# numpad.net
KiCad netlist of a schematic drawn in EAGLE
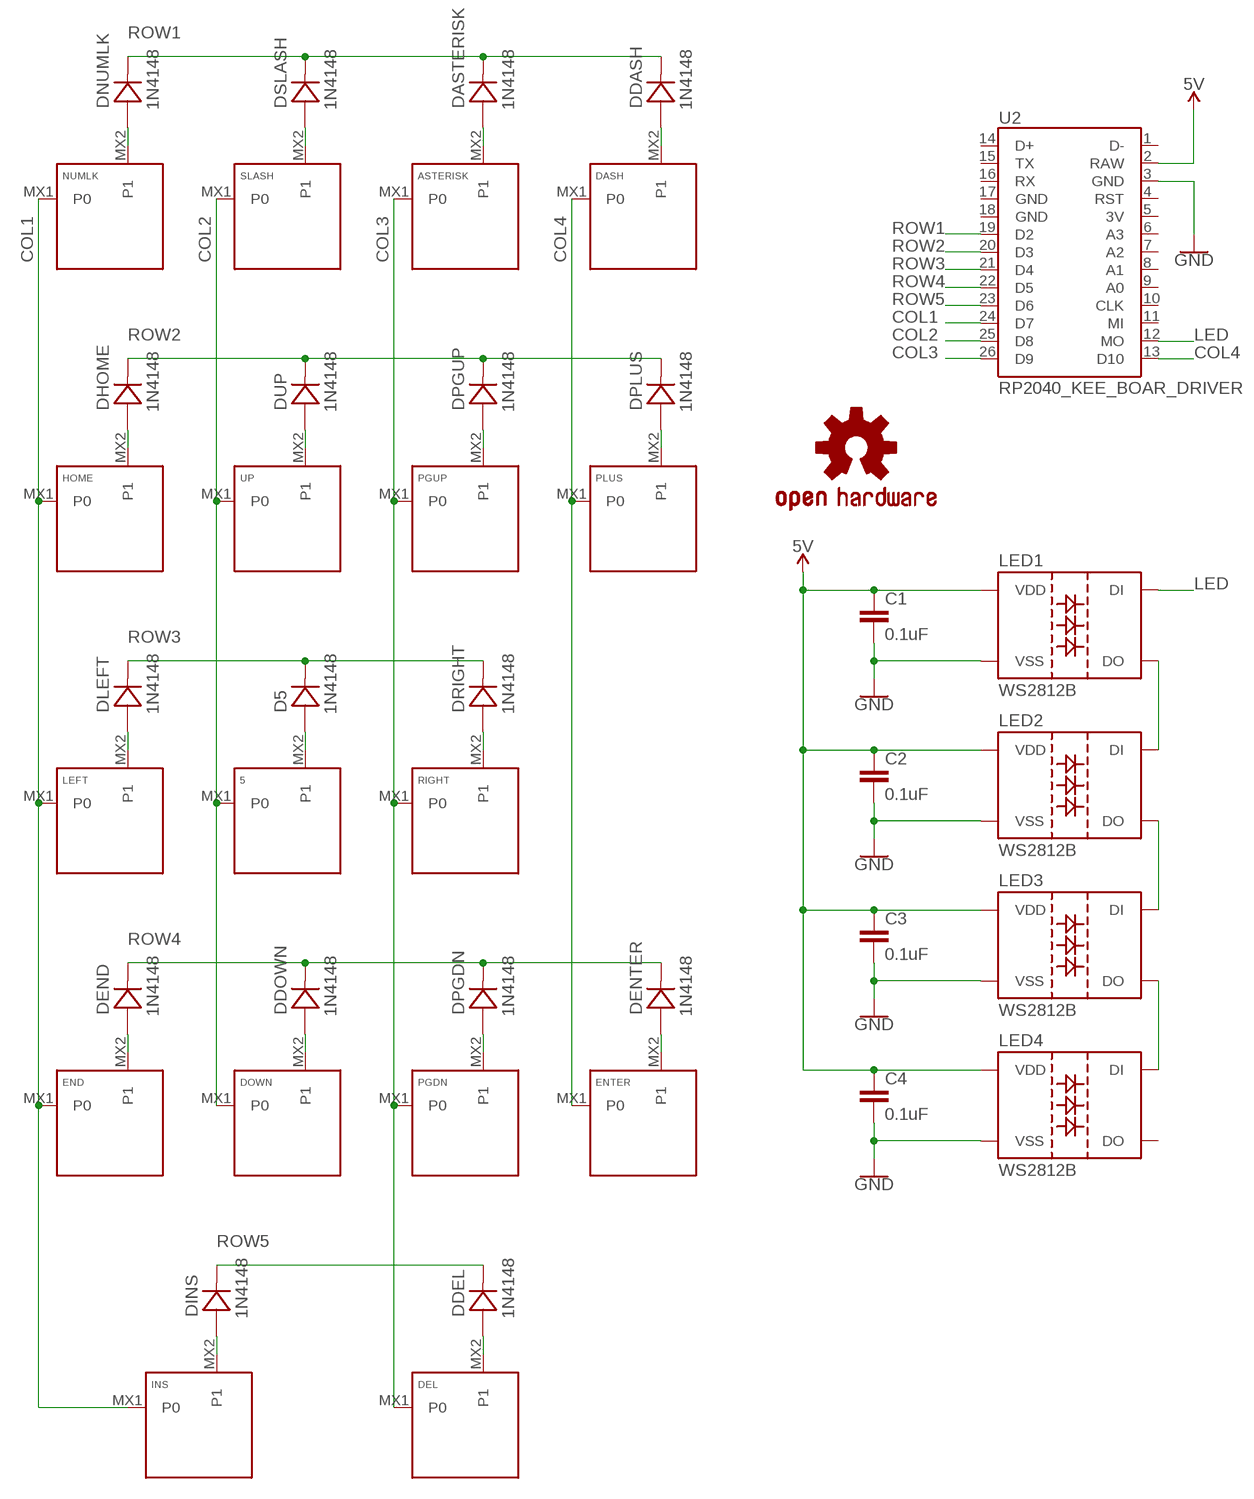
[diagram p0: schematic, sheet 1]

(export (version "E")
  (design (tool "Eeschema 10.0.6"))
  (components
    (comp (ref "5")
      (value "KEYSWITCH-PLAIN-MXHSPCB-1U")
      (footprint "eagle-import:MXHSPCB-1U")
      (libsource (lib "eagle-import") (part "KEYSWITCH-PLAIN-MXHSPCB-1U"))
    )
    (comp (ref "ASTERISK")
      (value "KEYSWITCH-PLAIN-MXHSPCB-1U")
      (footprint "eagle-import:MXHSPCB-1U")
      (libsource (lib "eagle-import") (part "KEYSWITCH-PLAIN-MXHSPCB-1U"))
    )
    (comp (ref "C1")
      (value "0.1uF")
      (footprint "eagle-import:0603")
      (libsource (lib "eagle-import") (part "0.1UF-0603-25V-(+80/-20%)"))
    )
    (comp (ref "C2")
      (value "0.1uF")
      (footprint "eagle-import:0603")
      (libsource (lib "eagle-import") (part "0.1UF-0603-25V-(+80/-20%)"))
    )
    (comp (ref "C3")
      (value "0.1uF")
      (footprint "eagle-import:0603")
      (libsource (lib "eagle-import") (part "0.1UF-0603-25V-(+80/-20%)"))
    )
    (comp (ref "C4")
      (value "0.1uF")
      (footprint "eagle-import:0603")
      (libsource (lib "eagle-import") (part "0.1UF-0603-25V-(+80/-20%)"))
    )
    (comp (ref "D5")
      (value "1N4148")
      (footprint "eagle-import:DO-35")
      (libsource (lib "eagle-import") (part "DIODE-DO-35"))
    )
    (comp (ref "DASH")
      (value "KEYSWITCH-PLAIN-MXHSPCB-1U")
      (footprint "eagle-import:MXHSPCB-1U")
      (libsource (lib "eagle-import") (part "KEYSWITCH-PLAIN-MXHSPCB-1U"))
    )
    (comp (ref "DASTERISK")
      (value "1N4148")
      (footprint "eagle-import:DO-35")
      (libsource (lib "eagle-import") (part "DIODE-DO-35"))
    )
    (comp (ref "DDASH")
      (value "1N4148")
      (footprint "eagle-import:DO-35")
      (libsource (lib "eagle-import") (part "DIODE-DO-35"))
    )
    (comp (ref "DDEL")
      (value "1N4148")
      (footprint "eagle-import:DO-35")
      (libsource (lib "eagle-import") (part "DIODE-DO-35"))
    )
    (comp (ref "DDOWN")
      (value "1N4148")
      (footprint "eagle-import:DO-35")
      (libsource (lib "eagle-import") (part "DIODE-DO-35"))
    )
    (comp (ref "DEL")
      (value "KEYSWITCH-PLAIN-MXHSPCB-1U")
      (footprint "eagle-import:MXHSPCB-1U")
      (libsource (lib "eagle-import") (part "KEYSWITCH-PLAIN-MXHSPCB-1U"))
    )
    (comp (ref "DEND")
      (value "1N4148")
      (footprint "eagle-import:DO-35")
      (libsource (lib "eagle-import") (part "DIODE-DO-35"))
    )
    (comp (ref "DENTER")
      (value "1N4148")
      (footprint "eagle-import:DO-35")
      (libsource (lib "eagle-import") (part "DIODE-DO-35"))
    )
    (comp (ref "DHOME")
      (value "1N4148")
      (footprint "eagle-import:DO-35")
      (libsource (lib "eagle-import") (part "DIODE-DO-35"))
    )
    (comp (ref "DINS")
      (value "1N4148")
      (footprint "eagle-import:DO-35")
      (libsource (lib "eagle-import") (part "DIODE-DO-35"))
    )
    (comp (ref "DLEFT")
      (value "1N4148")
      (footprint "eagle-import:DO-35")
      (libsource (lib "eagle-import") (part "DIODE-DO-35"))
    )
    (comp (ref "DNUMLK")
      (value "1N4148")
      (footprint "eagle-import:DO-35")
      (libsource (lib "eagle-import") (part "DIODE-DO-35"))
    )
    (comp (ref "DOWN")
      (value "KEYSWITCH-PLAIN-MXHSPCB-1U")
      (footprint "eagle-import:MXHSPCB-1U")
      (libsource (lib "eagle-import") (part "KEYSWITCH-PLAIN-MXHSPCB-1U"))
    )
    (comp (ref "DPGDN")
      (value "1N4148")
      (footprint "eagle-import:DO-35")
      (libsource (lib "eagle-import") (part "DIODE-DO-35"))
    )
    (comp (ref "DPGUP")
      (value "1N4148")
      (footprint "eagle-import:DO-35")
      (libsource (lib "eagle-import") (part "DIODE-DO-35"))
    )
    (comp (ref "DPLUS")
      (value "1N4148")
      (footprint "eagle-import:DO-35")
      (libsource (lib "eagle-import") (part "DIODE-DO-35"))
    )
    (comp (ref "DRIGHT")
      (value "1N4148")
      (footprint "eagle-import:DO-35")
      (libsource (lib "eagle-import") (part "DIODE-DO-35"))
    )
    (comp (ref "DSLASH")
      (value "1N4148")
      (footprint "eagle-import:DO-35")
      (libsource (lib "eagle-import") (part "DIODE-DO-35"))
    )
    (comp (ref "DUP")
      (value "1N4148")
      (footprint "eagle-import:DO-35")
      (libsource (lib "eagle-import") (part "DIODE-DO-35"))
    )
    (comp (ref "END")
      (value "KEYSWITCH-PLAIN-MXHSPCB-1U")
      (footprint "eagle-import:MXHSPCB-1U")
      (libsource (lib "eagle-import") (part "KEYSWITCH-PLAIN-MXHSPCB-1U"))
    )
    (comp (ref "ENTER")
      (value "KEYSWITCH-PLAIN-MXHSPCB-2U-ROTATED")
      (footprint "eagle-import:MXHSPCB-2U-ROTATED")
      (libsource (lib "eagle-import") (part "KEYSWITCH-PLAIN-MXHSPCB-2U-ROTATED"))
    )
    (comp (ref "HOME")
      (value "KEYSWITCH-PLAIN-MXHSPCB-1U")
      (footprint "eagle-import:MXHSPCB-1U")
      (libsource (lib "eagle-import") (part "KEYSWITCH-PLAIN-MXHSPCB-1U"))
    )
    (comp (ref "INS")
      (value "KEYSWITCH-PLAIN-MXHSPCB-2U")
      (footprint "eagle-import:MXHSPCB-2U")
      (libsource (lib "eagle-import") (part "KEYSWITCH-PLAIN-MXHSPCB-2U"))
    )
    (comp (ref "LED1")
      (value "WS2812B")
      (footprint "eagle-import:WS2812B")
      (libsource (lib "eagle-import") (part "WS2812B"))
    )
    (comp (ref "LED2")
      (value "WS2812B")
      (footprint "eagle-import:WS2812B")
      (libsource (lib "eagle-import") (part "WS2812B"))
    )
    (comp (ref "LED3")
      (value "WS2812B")
      (footprint "eagle-import:WS2812B")
      (libsource (lib "eagle-import") (part "WS2812B"))
    )
    (comp (ref "LED4")
      (value "WS2812B")
      (footprint "eagle-import:WS2812B")
      (libsource (lib "eagle-import") (part "WS2812B"))
    )
    (comp (ref "LEFT")
      (value "KEYSWITCH-PLAIN-MXHSPCB-1U")
      (footprint "eagle-import:MXHSPCB-1U")
      (libsource (lib "eagle-import") (part "KEYSWITCH-PLAIN-MXHSPCB-1U"))
    )
    (comp (ref "LOGO1")
      (value "OSHW-LOGOM")
      (footprint "eagle-import:OSHW-LOGO-M")
      (libsource (lib "eagle-import") (part "OSHW-LOGOM"))
    )
    (comp (ref "NUMLK")
      (value "KEYSWITCH-PLAIN-MXHSPCB-1U")
      (footprint "eagle-import:MXHSPCB-1U")
      (libsource (lib "eagle-import") (part "KEYSWITCH-PLAIN-MXHSPCB-1U"))
    )
    (comp (ref "PGDN")
      (value "KEYSWITCH-PLAIN-MXHSPCB-1U")
      (footprint "eagle-import:MXHSPCB-1U")
      (libsource (lib "eagle-import") (part "KEYSWITCH-PLAIN-MXHSPCB-1U"))
    )
    (comp (ref "PGUP")
      (value "KEYSWITCH-PLAIN-MXHSPCB-1U")
      (footprint "eagle-import:MXHSPCB-1U")
      (libsource (lib "eagle-import") (part "KEYSWITCH-PLAIN-MXHSPCB-1U"))
    )
    (comp (ref "PLUS")
      (value "KEYSWITCH-PLAIN-MXHSPCB-2U-ROTATED")
      (footprint "eagle-import:MXHSPCB-2U-ROTATED")
      (libsource (lib "eagle-import") (part "KEYSWITCH-PLAIN-MXHSPCB-2U-ROTATED"))
    )
    (comp (ref "RIGHT")
      (value "KEYSWITCH-PLAIN-MXHSPCB-1U")
      (footprint "eagle-import:MXHSPCB-1U")
      (libsource (lib "eagle-import") (part "KEYSWITCH-PLAIN-MXHSPCB-1U"))
    )
    (comp (ref "SLASH")
      (value "KEYSWITCH-PLAIN-MXHSPCB-1U")
      (footprint "eagle-import:MXHSPCB-1U")
      (libsource (lib "eagle-import") (part "KEYSWITCH-PLAIN-MXHSPCB-1U"))
    )
    (comp (ref "U2")
      (value "RP2040_KEE_BOAR_DRIVER")
      (footprint "eagle-import:RP2040_KEE_BOAR_DRIVER")
      (libsource (lib "eagle-import") (part "RP2040_KEE_BOAR_DRIVER"))
    )
    (comp (ref "UP")
      (value "KEYSWITCH-PLAIN-MXHSPCB-1U")
      (footprint "eagle-import:MXHSPCB-1U")
      (libsource (lib "eagle-import") (part "KEYSWITCH-PLAIN-MXHSPCB-1U"))
    )
  )
  (nets
    (net (code "1") (name "/COL1") (class "Default")
      (node (ref "END") (pin "MX1") (pinfunction "P0_MX1") (pintype "bidirectional"))
      (node (ref "HOME") (pin "MX1") (pinfunction "P0_MX1") (pintype "bidirectional"))
      (node (ref "INS") (pin "MX1") (pinfunction "P0_MX1") (pintype "bidirectional"))
      (node (ref "LEFT") (pin "MX1") (pinfunction "P0_MX1") (pintype "bidirectional"))
      (node (ref "NUMLK") (pin "MX1") (pinfunction "P0_MX1") (pintype "bidirectional"))
      (node (ref "U2") (pin "24") (pinfunction "D7_24") (pintype "bidirectional"))
    )
    (net (code "2") (name "/COL2") (class "Default")
      (node (ref "5") (pin "MX1") (pinfunction "P0_MX1") (pintype "bidirectional"))
      (node (ref "DOWN") (pin "MX1") (pinfunction "P0_MX1") (pintype "bidirectional"))
      (node (ref "SLASH") (pin "MX1") (pinfunction "P0_MX1") (pintype "bidirectional"))
      (node (ref "U2") (pin "25") (pinfunction "D8_25") (pintype "bidirectional"))
      (node (ref "UP") (pin "MX1") (pinfunction "P0_MX1") (pintype "bidirectional"))
    )
    (net (code "3") (name "/COL3") (class "Default")
      (node (ref "ASTERISK") (pin "MX1") (pinfunction "P0_MX1") (pintype "bidirectional"))
      (node (ref "DEL") (pin "MX1") (pinfunction "P0_MX1") (pintype "bidirectional"))
      (node (ref "PGDN") (pin "MX1") (pinfunction "P0_MX1") (pintype "bidirectional"))
      (node (ref "PGUP") (pin "MX1") (pinfunction "P0_MX1") (pintype "bidirectional"))
      (node (ref "RIGHT") (pin "MX1") (pinfunction "P0_MX1") (pintype "bidirectional"))
      (node (ref "U2") (pin "26") (pinfunction "D9_26") (pintype "bidirectional"))
    )
    (net (code "4") (name "/COL4") (class "Default")
      (node (ref "DASH") (pin "MX1") (pinfunction "P0_MX1") (pintype "bidirectional"))
      (node (ref "ENTER") (pin "MX1") (pinfunction "P0_MX1") (pintype "bidirectional"))
      (node (ref "PLUS") (pin "MX1") (pinfunction "P0_MX1") (pintype "bidirectional"))
      (node (ref "U2") (pin "13") (pinfunction "D10_13") (pintype "bidirectional"))
    )
    (net (code "5") (name "/LED") (class "Default")
      (node (ref "LED1") (pin "4") (pinfunction "DI_4") (pintype "bidirectional"))
      (node (ref "U2") (pin "12") (pinfunction "MO_12") (pintype "bidirectional"))
    )
    (net (code "6") (name "/ROW1") (class "Default")
      (node (ref "DASTERISK") (pin "C") (pinfunction "C_C") (pintype "passive"))
      (node (ref "DDASH") (pin "C") (pinfunction "C_C") (pintype "passive"))
      (node (ref "DNUMLK") (pin "C") (pinfunction "C_C") (pintype "passive"))
      (node (ref "DSLASH") (pin "C") (pinfunction "C_C") (pintype "passive"))
      (node (ref "U2") (pin "19") (pinfunction "D2_19") (pintype "bidirectional"))
    )
    (net (code "7") (name "/ROW2") (class "Default")
      (node (ref "DHOME") (pin "C") (pinfunction "C_C") (pintype "passive"))
      (node (ref "DPGUP") (pin "C") (pinfunction "C_C") (pintype "passive"))
      (node (ref "DPLUS") (pin "C") (pinfunction "C_C") (pintype "passive"))
      (node (ref "DUP") (pin "C") (pinfunction "C_C") (pintype "passive"))
      (node (ref "U2") (pin "20") (pinfunction "D3_20") (pintype "bidirectional"))
    )
    (net (code "8") (name "/ROW3") (class "Default")
      (node (ref "D5") (pin "C") (pinfunction "C_C") (pintype "passive"))
      (node (ref "DLEFT") (pin "C") (pinfunction "C_C") (pintype "passive"))
      (node (ref "DRIGHT") (pin "C") (pinfunction "C_C") (pintype "passive"))
      (node (ref "U2") (pin "21") (pinfunction "D4_21") (pintype "bidirectional"))
    )
    (net (code "9") (name "/ROW4") (class "Default")
      (node (ref "DDOWN") (pin "C") (pinfunction "C_C") (pintype "passive"))
      (node (ref "DEND") (pin "C") (pinfunction "C_C") (pintype "passive"))
      (node (ref "DENTER") (pin "C") (pinfunction "C_C") (pintype "passive"))
      (node (ref "DPGDN") (pin "C") (pinfunction "C_C") (pintype "passive"))
      (node (ref "U2") (pin "22") (pinfunction "D5_22") (pintype "bidirectional"))
    )
    (net (code "10") (name "/ROW5") (class "Default")
      (node (ref "DDEL") (pin "C") (pinfunction "C_C") (pintype "passive"))
      (node (ref "DINS") (pin "C") (pinfunction "C_C") (pintype "passive"))
      (node (ref "U2") (pin "23") (pinfunction "D6_23") (pintype "bidirectional"))
    )
    (net (code "11") (name "5V") (class "Default")
      (node (ref "C1") (pin "1") (pinfunction "1_1") (pintype "passive"))
      (node (ref "C2") (pin "1") (pinfunction "1_1") (pintype "passive"))
      (node (ref "C3") (pin "1") (pinfunction "1_1") (pintype "passive"))
      (node (ref "C4") (pin "1") (pinfunction "1_1") (pintype "passive"))
      (node (ref "LED1") (pin "1") (pinfunction "VDD_1") (pintype "bidirectional"))
      (node (ref "LED2") (pin "1") (pinfunction "VDD_1") (pintype "bidirectional"))
      (node (ref "LED3") (pin "1") (pinfunction "VDD_1") (pintype "bidirectional"))
      (node (ref "LED4") (pin "1") (pinfunction "VDD_1") (pintype "bidirectional"))
      (node (ref "U2") (pin "2") (pinfunction "RAW_2") (pintype "bidirectional"))
    )
    (net (code "12") (name "GND") (class "Default")
      (node (ref "C1") (pin "2") (pinfunction "2_2") (pintype "passive"))
      (node (ref "C2") (pin "2") (pinfunction "2_2") (pintype "passive"))
      (node (ref "C3") (pin "2") (pinfunction "2_2") (pintype "passive"))
      (node (ref "C4") (pin "2") (pinfunction "2_2") (pintype "passive"))
      (node (ref "LED1") (pin "3") (pinfunction "VSS_3") (pintype "bidirectional"))
      (node (ref "LED2") (pin "3") (pinfunction "VSS_3") (pintype "bidirectional"))
      (node (ref "LED3") (pin "3") (pinfunction "VSS_3") (pintype "bidirectional"))
      (node (ref "LED4") (pin "3") (pinfunction "VSS_3") (pintype "bidirectional"))
      (node (ref "U2") (pin "3") (pinfunction "GND_3") (pintype "bidirectional"))
    )
    (net (code "13") (name "Net-(5-P1)") (class "Default")
      (node (ref "5") (pin "MX2") (pinfunction "P1_MX2") (pintype "bidirectional"))
      (node (ref "D5") (pin "A") (pinfunction "A_A") (pintype "passive"))
    )
    (net (code "14") (name "Net-(ASTERISK-P1)") (class "Default")
      (node (ref "ASTERISK") (pin "MX2") (pinfunction "P1_MX2") (pintype "bidirectional"))
      (node (ref "DASTERISK") (pin "A") (pinfunction "A_A") (pintype "passive"))
    )
    (net (code "15") (name "Net-(DASH-P1)") (class "Default")
      (node (ref "DASH") (pin "MX2") (pinfunction "P1_MX2") (pintype "bidirectional"))
      (node (ref "DDASH") (pin "A") (pinfunction "A_A") (pintype "passive"))
    )
    (net (code "16") (name "Net-(DEL-P1)") (class "Default")
      (node (ref "DDEL") (pin "A") (pinfunction "A_A") (pintype "passive"))
      (node (ref "DEL") (pin "MX2") (pinfunction "P1_MX2") (pintype "bidirectional"))
    )
    (net (code "17") (name "Net-(DOWN-P1)") (class "Default")
      (node (ref "DDOWN") (pin "A") (pinfunction "A_A") (pintype "passive"))
      (node (ref "DOWN") (pin "MX2") (pinfunction "P1_MX2") (pintype "bidirectional"))
    )
    (net (code "18") (name "Net-(END-P1)") (class "Default")
      (node (ref "DEND") (pin "A") (pinfunction "A_A") (pintype "passive"))
      (node (ref "END") (pin "MX2") (pinfunction "P1_MX2") (pintype "bidirectional"))
    )
    (net (code "19") (name "Net-(ENTER-P1)") (class "Default")
      (node (ref "DENTER") (pin "A") (pinfunction "A_A") (pintype "passive"))
      (node (ref "ENTER") (pin "MX2") (pinfunction "P1_MX2") (pintype "bidirectional"))
    )
    (net (code "20") (name "Net-(HOME-P1)") (class "Default")
      (node (ref "DHOME") (pin "A") (pinfunction "A_A") (pintype "passive"))
      (node (ref "HOME") (pin "MX2") (pinfunction "P1_MX2") (pintype "bidirectional"))
    )
    (net (code "21") (name "Net-(INS-P1)") (class "Default")
      (node (ref "DINS") (pin "A") (pinfunction "A_A") (pintype "passive"))
      (node (ref "INS") (pin "MX2") (pinfunction "P1_MX2") (pintype "bidirectional"))
    )
    (net (code "22") (name "Net-(LED1-DO)") (class "Default")
      (node (ref "LED1") (pin "2") (pinfunction "DO_2") (pintype "bidirectional"))
      (node (ref "LED2") (pin "4") (pinfunction "DI_4") (pintype "bidirectional"))
    )
    (net (code "23") (name "Net-(LED2-DO)") (class "Default")
      (node (ref "LED2") (pin "2") (pinfunction "DO_2") (pintype "bidirectional"))
      (node (ref "LED3") (pin "4") (pinfunction "DI_4") (pintype "bidirectional"))
    )
    (net (code "24") (name "Net-(LED3-DO)") (class "Default")
      (node (ref "LED3") (pin "2") (pinfunction "DO_2") (pintype "bidirectional"))
      (node (ref "LED4") (pin "4") (pinfunction "DI_4") (pintype "bidirectional"))
    )
    (net (code "25") (name "Net-(LEFT-P1)") (class "Default")
      (node (ref "DLEFT") (pin "A") (pinfunction "A_A") (pintype "passive"))
      (node (ref "LEFT") (pin "MX2") (pinfunction "P1_MX2") (pintype "bidirectional"))
    )
    (net (code "26") (name "Net-(NUMLK-P1)") (class "Default")
      (node (ref "DNUMLK") (pin "A") (pinfunction "A_A") (pintype "passive"))
      (node (ref "NUMLK") (pin "MX2") (pinfunction "P1_MX2") (pintype "bidirectional"))
    )
    (net (code "27") (name "Net-(PGDN-P1)") (class "Default")
      (node (ref "DPGDN") (pin "A") (pinfunction "A_A") (pintype "passive"))
      (node (ref "PGDN") (pin "MX2") (pinfunction "P1_MX2") (pintype "bidirectional"))
    )
    (net (code "28") (name "Net-(PGUP-P1)") (class "Default")
      (node (ref "DPGUP") (pin "A") (pinfunction "A_A") (pintype "passive"))
      (node (ref "PGUP") (pin "MX2") (pinfunction "P1_MX2") (pintype "bidirectional"))
    )
    (net (code "29") (name "Net-(PLUS-P1)") (class "Default")
      (node (ref "DPLUS") (pin "A") (pinfunction "A_A") (pintype "passive"))
      (node (ref "PLUS") (pin "MX2") (pinfunction "P1_MX2") (pintype "bidirectional"))
    )
    (net (code "30") (name "Net-(RIGHT-P1)") (class "Default")
      (node (ref "DRIGHT") (pin "A") (pinfunction "A_A") (pintype "passive"))
      (node (ref "RIGHT") (pin "MX2") (pinfunction "P1_MX2") (pintype "bidirectional"))
    )
    (net (code "31") (name "Net-(SLASH-P1)") (class "Default")
      (node (ref "DSLASH") (pin "A") (pinfunction "A_A") (pintype "passive"))
      (node (ref "SLASH") (pin "MX2") (pinfunction "P1_MX2") (pintype "bidirectional"))
    )
    (net (code "32") (name "Net-(UP-P1)") (class "Default")
      (node (ref "DUP") (pin "A") (pinfunction "A_A") (pintype "passive"))
      (node (ref "UP") (pin "MX2") (pinfunction "P1_MX2") (pintype "bidirectional"))
    )
    (net (code "33") (name "unconnected-(LED4-DO-Pad2)") (class "Default")
      (node (ref "LED4") (pin "2") (pinfunction "DO_2") (pintype "bidirectional"))
    )
    (net (code "34") (name "unconnected-(U2-3V-Pad5)") (class "Default")
      (node (ref "U2") (pin "5") (pinfunction "3V_5") (pintype "bidirectional"))
    )
    (net (code "35") (name "unconnected-(U2-A0-Pad9)") (class "Default")
      (node (ref "U2") (pin "9") (pinfunction "A0_9") (pintype "bidirectional"))
    )
    (net (code "36") (name "unconnected-(U2-A1-Pad8)") (class "Default")
      (node (ref "U2") (pin "8") (pinfunction "A1_8") (pintype "bidirectional"))
    )
    (net (code "37") (name "unconnected-(U2-A2-Pad7)") (class "Default")
      (node (ref "U2") (pin "7") (pinfunction "A2_7") (pintype "bidirectional"))
    )
    (net (code "38") (name "unconnected-(U2-A3-Pad6)") (class "Default")
      (node (ref "U2") (pin "6") (pinfunction "A3_6") (pintype "bidirectional"))
    )
    (net (code "39") (name "unconnected-(U2-CLK-Pad10)") (class "Default")
      (node (ref "U2") (pin "10") (pinfunction "CLK_10") (pintype "bidirectional"))
    )
    (net (code "40") (name "unconnected-(U2-D+-Pad14)") (class "Default")
      (node (ref "U2") (pin "14") (pinfunction "D+_14") (pintype "bidirectional"))
    )
    (net (code "41") (name "unconnected-(U2-D--Pad1)") (class "Default")
      (node (ref "U2") (pin "1") (pinfunction "D-_1") (pintype "bidirectional"))
    )
    (net (code "42") (name "unconnected-(U2-GND-Pad17)") (class "Default")
      (node (ref "U2") (pin "17") (pinfunction "GND_17") (pintype "bidirectional"))
    )
    (net (code "43") (name "unconnected-(U2-GND-Pad18)") (class "Default")
      (node (ref "U2") (pin "18") (pinfunction "GND_18") (pintype "bidirectional"))
    )
    (net (code "44") (name "unconnected-(U2-MI-Pad11)") (class "Default")
      (node (ref "U2") (pin "11") (pinfunction "MI_11") (pintype "bidirectional"))
    )
    (net (code "45") (name "unconnected-(U2-RST-Pad4)") (class "Default")
      (node (ref "U2") (pin "4") (pinfunction "RST_4") (pintype "bidirectional"))
    )
    (net (code "46") (name "unconnected-(U2-RX-Pad16)") (class "Default")
      (node (ref "U2") (pin "16") (pinfunction "RX_16") (pintype "bidirectional"))
    )
    (net (code "47") (name "unconnected-(U2-TX-Pad15)") (class "Default")
      (node (ref "U2") (pin "15") (pinfunction "TX_15") (pintype "bidirectional"))
    )
  )
)
